# Sheet1.net
KiCad netlist of a schematic drawn in Altium Designer
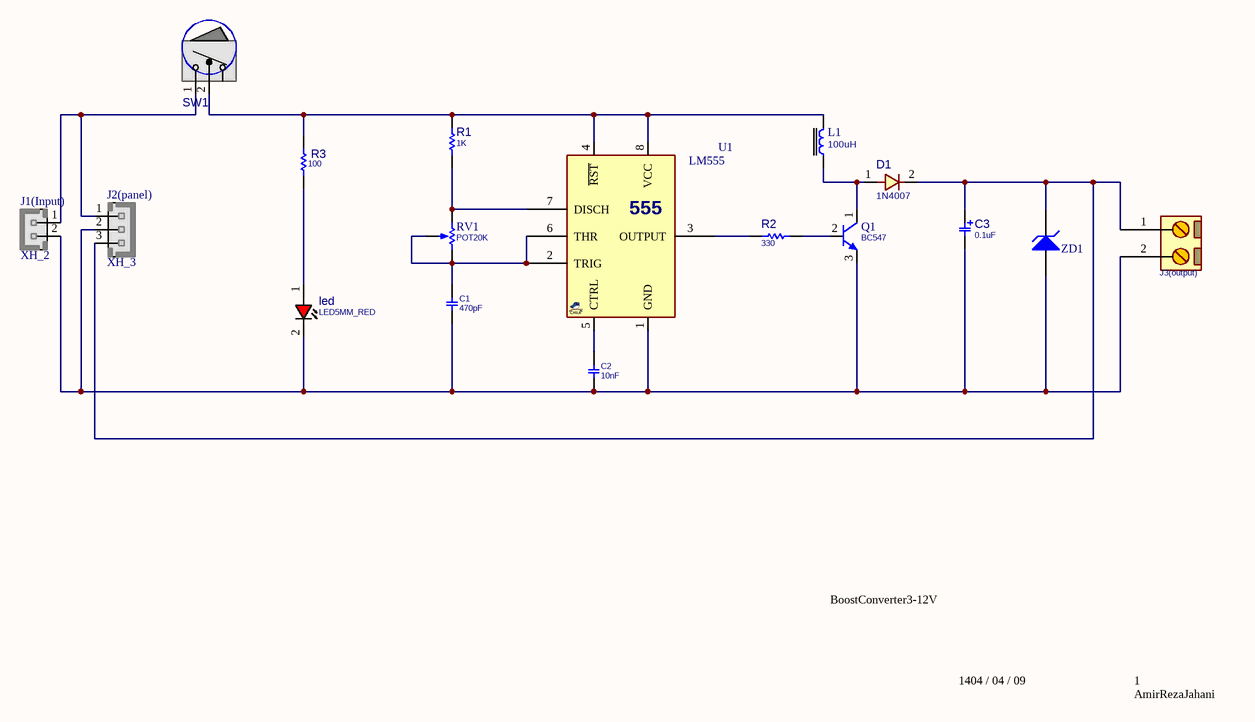
[diagram p0: Sheet1.SchDoc]

(export (version "E")
  (design (tool "Eeschema 10.0.6"))
  (components
    (comp (ref "C1")
      (value "470pF")
      (footprint "C_CER_D5")
      (description "CAP, THD, CER MULTI LAYER,")
      (fields (field (name "MANF_P#") "MANF_PART#") (field (name "MANF") "MANF"))
      (libsource (lib "passive_thd") (part "CAP_THD_CER"))
    )
    (comp (ref "C2")
      (value "10nF")
      (footprint "C_CER_D5")
      (description "CAP, THD, CER MULTI LAYER,")
      (fields (field (name "MANF_P#") "MANF_PART#") (field (name "MANF") "MANF"))
      (libsource (lib "passive_thd") (part "CAP_THD_CER"))
    )
    (comp (ref "C3")
      (value "0.1uF")
      (footprint "C_EL_12X25")
      (description "CAP, THD, ELEC,")
      (fields (field (name "MANF_P#") "MANF_PART#") (field (name "MANF") "MANF"))
      (libsource (lib "passive_thd") (part "CAP_THD_EL"))
    )
    (comp (ref "D1")
      (value "1N4007")
      (footprint "D_AX04_DO41")
      (description "DIODE, THD")
      (fields (field (name "MANF") "MANF") (field (name "MANF_P#") "1N4001"))
      (libsource (lib "diode") (part "DIODE_THD"))
    )
    (comp (ref "J1(Input)")
      (value "XH_2")
      (footprint "XH_2")
      (description "PW10-x-M, JST-BxB-XH-A pitch: 2.5mm, 3A/250v")
      (fields (field (name "MANF") "JST") (field (name "MANF_P#") "B2B-XH-A"))
      (libsource (lib "conn_wire2board") (part "XH_2"))
    )
    (comp (ref "J2(panel)")
      (value "XH_3")
      (footprint "XH_3")
      (description "PW10-x-M, JST-BxB-XH-A pitch: 2.5mm, 3A/250v")
      (fields (field (name "MANF") "JST") (field (name "MANF_P#") "B3B-XH-A"))
      (libsource (lib "conn_wire2board") (part "XH_3"))
    )
    (comp (ref "J3(output)")
      (value "CONN_TB2")
      (footprint "TBB_2")
      (description "CONN, TERMINAL BLOCK, 5.08mm pitch")
      (libsource (lib "conn_terminalB") (part "CONN_TB2"))
    )
    (comp (ref "L1")
      (value "100uH")
      (footprint "LTOR_25X10")
      (description "INDUCTOR, THD")
      (libsource (lib "passive_thd") (part "IND_THD"))
    )
    (comp (ref "led")
      (value "LED5MM_RED")
      (footprint "LED5MM_RED")
      (description "LED, THD, 5MM, RED")
      (fields (field (name "MANF") "MANF") (field (name "MANF_P#") "MANF_PART#"))
      (libsource (lib "led(diode)") (part "LED_THD_5MM_RED"))
    )
    (comp (ref "Q1")
      (value "BC547")
      (footprint "TO92_3")
      (description "BJT, NPN, 45v, 0.1A, THD, TO92")
      (fields (field (name "MANF") "FAIRCHILD"))
      (libsource (lib "transistor_bjt") (part "NPN_BC547_TO92"))
    )
    (comp (ref "R1")
      (value "1K")
      (footprint "R025W_AX04")
      (description "RESISTOR, THD")
      (fields (field (name "MANF_P#") "RK73H1ETTP4701F") (field (name "MANF") "KOA SPEER"))
      (libsource (lib "passive_thd") (part "RES_THD"))
    )
    (comp (ref "R2")
      (value "330")
      (footprint "R025W_AX04")
      (description "RESISTOR, THD")
      (fields (field (name "MANF_P#") "RK73H1ETTP4701F") (field (name "MANF") "KOA SPEER"))
      (libsource (lib "passive_thd") (part "RES_THD"))
    )
    (comp (ref "R3")
      (value "100")
      (footprint "R025W_AX04")
      (description "RESISTOR, THD")
      (fields (field (name "MANF_P#") "RK73H1ETTP4701F") (field (name "MANF") "KOA SPEER"))
      (libsource (lib "passive_thd") (part "RES_THD"))
    )
    (comp (ref "RV1")
      (value "POT20K")
      (footprint "VOL_R")
      (description "RESISTOR, THD, Potentiometer Volume")
      (libsource (lib "resistor_pot_trimmer") (part "RES_THD_POT_VOL"))
    )
    (comp (ref "SW1")
      (value "ToggleSwitch")
      (footprint "SWRCK_SPST_S_15X10")
      (description "SWITCH, Rocker, SPST, THD, 15x10.5mm")
      (libsource (lib "switch_rocker") (part "SWROK_SPST_R_15X10"))
    )
    (comp (ref "U1")
      (value "LM555")
      (footprint "DIP_8")
      (description "555 Timer,")
      (fields (field (name "MANF") "Fairchild, Texas Instruments") (field (name "MANF_P#") "LM555CN"))
      (libsource (lib "ic_timer_555") (part "LM555_DIP8"))
    )
    (comp (ref "ZD1")
      (value "Diode Zener")
      (footprint "Diode 1W")
      (description "Zener Diode")
      (fields (field (name "VOLTAGE") "3.3 V") (field (name "DESIGNER") "Saeid Jorablo"))
      (libsource (lib "My_Library") (part "Diode Zener"))
    )
  )
  (nets
    (net (code "1") (name "Net-(Q1-B)") (class "Default")
      (node (ref "Q1") (pin "2") (pinfunction "B_2") (pintype "passive"))
      (node (ref "R2") (pin "2") (pinfunction "2_2") (pintype "passive"))
    )
    (net (code "2") (name "Net-(Q1-C)") (class "Default")
      (node (ref "D1") (pin "1") (pinfunction "1_1") (pintype "passive"))
      (node (ref "L1") (pin "1") (pinfunction "1_1") (pintype "passive"))
      (node (ref "Q1") (pin "1") (pinfunction "C_1") (pintype "passive"))
    )
    (net (code "3") (name "Net-(Q1-E)") (class "Default")
      (node (ref "C1") (pin "1") (pinfunction "1_1") (pintype "passive"))
      (node (ref "C2") (pin "1") (pinfunction "1_1") (pintype "passive"))
      (node (ref "C3") (pin "2") (pinfunction "2_2") (pintype "passive"))
      (node (ref "J1(Input)") (pin "2") (pinfunction "2_2") (pintype "passive"))
      (node (ref "J2(panel)") (pin "2") (pinfunction "2_2") (pintype "passive"))
      (node (ref "J3(output)") (pin "2") (pinfunction "2_2") (pintype "passive"))
      (node (ref "Q1") (pin "3") (pinfunction "E_3") (pintype "passive"))
      (node (ref "U1") (pin "1") (pinfunction "GND_1") (pintype "passive"))
      (node (ref "ZD1") (pin "1") (pinfunction "A_1") (pintype "passive"))
      (node (ref "led") (pin "2") (pinfunction "CATHODE_2") (pintype "passive"))
    )
    (net (code "4") (name "Net-(RV1-BOT)") (class "Default")
      (node (ref "C1") (pin "2") (pinfunction "2_2") (pintype "passive"))
      (node (ref "RV1") (pin "2") (pinfunction "TAP_2") (pintype "passive"))
      (node (ref "RV1") (pin "3") (pinfunction "BOT_3") (pintype "passive"))
      (node (ref "U1") (pin "2") (pinfunction "TRIG_2") (pintype "passive"))
      (node (ref "U1") (pin "6") (pinfunction "THR_6") (pintype "passive"))
    )
    (net (code "5") (name "Net-(RV1-TOP)") (class "Default")
      (node (ref "R1") (pin "1") (pinfunction "1_1") (pintype "passive"))
      (node (ref "RV1") (pin "1") (pinfunction "TOP_1") (pintype "passive"))
      (node (ref "U1") (pin "7") (pinfunction "DISCH_7") (pintype "passive"))
    )
    (net (code "6") (name "Net-(SW1-COM)") (class "Default")
      (node (ref "L1") (pin "2") (pinfunction "2_2") (pintype "passive"))
      (node (ref "R1") (pin "2") (pinfunction "2_2") (pintype "passive"))
      (node (ref "R3") (pin "2") (pinfunction "2_2") (pintype "passive"))
      (node (ref "SW1") (pin "2") (pinfunction "COM_2") (pintype "passive"))
      (node (ref "U1") (pin "4") (pinfunction "~{RST}_4") (pintype "passive"))
      (node (ref "U1") (pin "8") (pinfunction "VCC_8") (pintype "passive"))
    )
    (net (code "7") (name "Net-(SW1-T1)") (class "Default")
      (node (ref "J1(Input)") (pin "1") (pinfunction "1_1") (pintype "passive"))
      (node (ref "J2(panel)") (pin "1") (pinfunction "1_1") (pintype "passive"))
      (node (ref "SW1") (pin "1") (pinfunction "T1_1") (pintype "passive"))
    )
    (net (code "8") (name "Net-(U1-CTRL)") (class "Default")
      (node (ref "C2") (pin "2") (pinfunction "2_2") (pintype "passive"))
      (node (ref "U1") (pin "5") (pinfunction "CTRL_5") (pintype "passive"))
    )
    (net (code "9") (name "Net-(U1-OUTPUT)") (class "Default")
      (node (ref "R2") (pin "1") (pinfunction "1_1") (pintype "passive"))
      (node (ref "U1") (pin "3") (pinfunction "OUTPUT_3") (pintype "passive"))
    )
    (net (code "10") (name "Net-(ZD1-K)") (class "Default")
      (node (ref "C3") (pin "1") (pinfunction "1_1") (pintype "passive"))
      (node (ref "D1") (pin "2") (pinfunction "2_2") (pintype "passive"))
      (node (ref "J2(panel)") (pin "3") (pinfunction "3_3") (pintype "passive"))
      (node (ref "J3(output)") (pin "1") (pinfunction "1_1") (pintype "passive"))
      (node (ref "ZD1") (pin "2") (pinfunction "K_2") (pintype "passive"))
    )
    (net (code "11") (name "Net-(led-ANODE)") (class "Default")
      (node (ref "R3") (pin "1") (pinfunction "1_1") (pintype "passive"))
      (node (ref "led") (pin "1") (pinfunction "ANODE_1") (pintype "passive"))
    )
  )
)
